# SMDled-mosfet.net
KiCad netlist of a schematic drawn in EAGLE
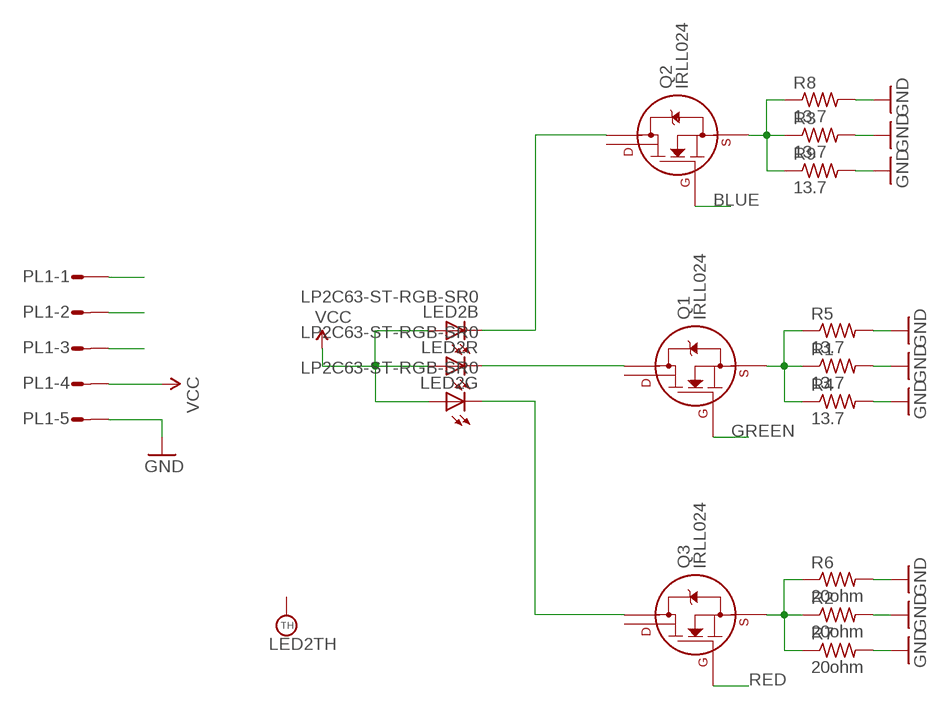
[diagram p0: schematic, sheet 1]

(export (version "E")
  (design (tool "Eeschema 10.0.6"))
  (components
    (comp (ref "LED2")
      (value "LP2C63-ST-RGB-SR0")
      (footprint "eagle-import:LP2C63-ST-RGB-SR0")
      (libsource (lib "eagle-import") (part "LP2C63-ST-RGB-SR0"))
    )
    (comp (ref "PL1")
      (value "DF3-05R")
      (footprint "eagle-import:DF3R-05")
      (libsource (lib "eagle-import") (part "DF3-05R"))
    )
    (comp (ref "Q1")
      (value "IRLL024")
      (footprint "eagle-import:SOT-223")
      (libsource (lib "eagle-import") (part "IRLL024"))
    )
    (comp (ref "Q2")
      (value "IRLL024")
      (footprint "eagle-import:SOT-223")
      (libsource (lib "eagle-import") (part "IRLL024"))
    )
    (comp (ref "Q3")
      (value "IRLL024")
      (footprint "eagle-import:SOT-223")
      (libsource (lib "eagle-import") (part "IRLL024"))
    )
    (comp (ref "R1")
      (value "13.7")
      (footprint "eagle-import:R1210")
      (libsource (lib "eagle-import") (part "R-US_R1210"))
    )
    (comp (ref "R2")
      (value "20ohm")
      (footprint "eagle-import:R1210")
      (libsource (lib "eagle-import") (part "R-US_R1210"))
    )
    (comp (ref "R3")
      (value "13.7")
      (footprint "eagle-import:R1210")
      (libsource (lib "eagle-import") (part "R-US_R1210"))
    )
    (comp (ref "R4")
      (value "13.7")
      (footprint "eagle-import:R1210")
      (libsource (lib "eagle-import") (part "R-US_R1210"))
    )
    (comp (ref "R5")
      (value "13.7")
      (footprint "eagle-import:R1210")
      (libsource (lib "eagle-import") (part "R-US_R1210"))
    )
    (comp (ref "R6")
      (value "20ohm")
      (footprint "eagle-import:R1210")
      (libsource (lib "eagle-import") (part "R-US_R1210"))
    )
    (comp (ref "R7")
      (value "20ohm")
      (footprint "eagle-import:R1210")
      (libsource (lib "eagle-import") (part "R-US_R1210"))
    )
    (comp (ref "R8")
      (value "13.7")
      (footprint "eagle-import:R1210")
      (libsource (lib "eagle-import") (part "R-US_R1210"))
    )
    (comp (ref "R9")
      (value "13.7")
      (footprint "eagle-import:R1210")
      (libsource (lib "eagle-import") (part "R-US_R1210"))
    )
  )
  (nets
    (net (code "1") (name "/BLUE") (class "Default")
      (node (ref "PL1") (pin "3") (pinfunction "S_3") (pintype "passive"))
      (node (ref "Q2") (pin "1") (pinfunction "G_1") (pintype "tri_state"))
    )
    (net (code "2") (name "/GREEN") (class "Default")
      (node (ref "PL1") (pin "1") (pinfunction "S_1") (pintype "passive"))
      (node (ref "Q1") (pin "1") (pinfunction "G_1") (pintype "tri_state"))
    )
    (net (code "3") (name "/RED") (class "Default")
      (node (ref "PL1") (pin "2") (pinfunction "S_2") (pintype "passive"))
      (node (ref "Q3") (pin "1") (pinfunction "G_1") (pintype "tri_state"))
    )
    (net (code "4") (name "GND") (class "Default")
      (node (ref "PL1") (pin "5") (pinfunction "S_5") (pintype "passive"))
      (node (ref "R1") (pin "2") (pinfunction "2_2") (pintype "passive"))
      (node (ref "R2") (pin "2") (pinfunction "2_2") (pintype "passive"))
      (node (ref "R3") (pin "2") (pinfunction "2_2") (pintype "passive"))
      (node (ref "R4") (pin "2") (pinfunction "2_2") (pintype "passive"))
      (node (ref "R5") (pin "2") (pinfunction "2_2") (pintype "passive"))
      (node (ref "R6") (pin "2") (pinfunction "2_2") (pintype "passive"))
      (node (ref "R7") (pin "2") (pinfunction "2_2") (pintype "passive"))
      (node (ref "R8") (pin "2") (pinfunction "2_2") (pintype "passive"))
      (node (ref "R9") (pin "2") (pinfunction "2_2") (pintype "passive"))
    )
    (net (code "5") (name "Net-(LED2A-C)") (class "Default")
      (node (ref "LED2") (pin "4") (pinfunction "C_4") (pintype "passive"))
      (node (ref "Q2") (pin "2") (pinfunction "D1_2") (pintype "bidirectional"))
    )
    (net (code "6") (name "Net-(LED2B-C)") (class "Default")
      (node (ref "LED2") (pin "6") (pinfunction "C_6") (pintype "passive"))
      (node (ref "Q3") (pin "2") (pinfunction "D1_2") (pintype "bidirectional"))
    )
    (net (code "7") (name "Net-(LED2C-C)") (class "Default")
      (node (ref "LED2") (pin "5") (pinfunction "C_5") (pintype "passive"))
      (node (ref "Q1") (pin "2") (pinfunction "D1_2") (pintype "bidirectional"))
    )
    (net (code "8") (name "Net-(Q1-S)") (class "Default")
      (node (ref "Q1") (pin "3") (pinfunction "S_3") (pintype "bidirectional"))
      (node (ref "R1") (pin "1") (pinfunction "1_1") (pintype "passive"))
      (node (ref "R4") (pin "1") (pinfunction "1_1") (pintype "passive"))
      (node (ref "R5") (pin "1") (pinfunction "1_1") (pintype "passive"))
    )
    (net (code "9") (name "Net-(Q2-S)") (class "Default")
      (node (ref "Q2") (pin "3") (pinfunction "S_3") (pintype "bidirectional"))
      (node (ref "R3") (pin "1") (pinfunction "1_1") (pintype "passive"))
      (node (ref "R8") (pin "1") (pinfunction "1_1") (pintype "passive"))
      (node (ref "R9") (pin "1") (pinfunction "1_1") (pintype "passive"))
    )
    (net (code "10") (name "Net-(Q3-S)") (class "Default")
      (node (ref "Q3") (pin "3") (pinfunction "S_3") (pintype "bidirectional"))
      (node (ref "R2") (pin "1") (pinfunction "1_1") (pintype "passive"))
      (node (ref "R6") (pin "1") (pinfunction "1_1") (pintype "passive"))
      (node (ref "R7") (pin "1") (pinfunction "1_1") (pintype "passive"))
    )
    (net (code "11") (name "VCC") (class "Default")
      (node (ref "LED2") (pin "1") (pinfunction "A_1") (pintype "passive"))
      (node (ref "LED2") (pin "2") (pinfunction "A_2") (pintype "passive"))
      (node (ref "LED2") (pin "3") (pinfunction "A_3") (pintype "passive"))
      (node (ref "PL1") (pin "4") (pinfunction "S_4") (pintype "passive"))
    )
    (net (code "12") (name "unconnected-(LED2-PadTH)") (class "Default")
      (node (ref "LED2") (pin "TH") (pinfunction "TH_TH") (pintype "passive"))
    )
    (net (code "13") (name "unconnected-(Q1-D2-Pad4)") (class "Default")
      (node (ref "Q1") (pin "4") (pinfunction "D2_4") (pintype "bidirectional"))
    )
    (net (code "14") (name "unconnected-(Q2-D2-Pad4)") (class "Default")
      (node (ref "Q2") (pin "4") (pinfunction "D2_4") (pintype "bidirectional"))
    )
    (net (code "15") (name "unconnected-(Q3-D2-Pad4)") (class "Default")
      (node (ref "Q3") (pin "4") (pinfunction "D2_4") (pintype "bidirectional"))
    )
  )
)
